# TMS.net
KiCad netlist of a schematic drawn in Altium Designer
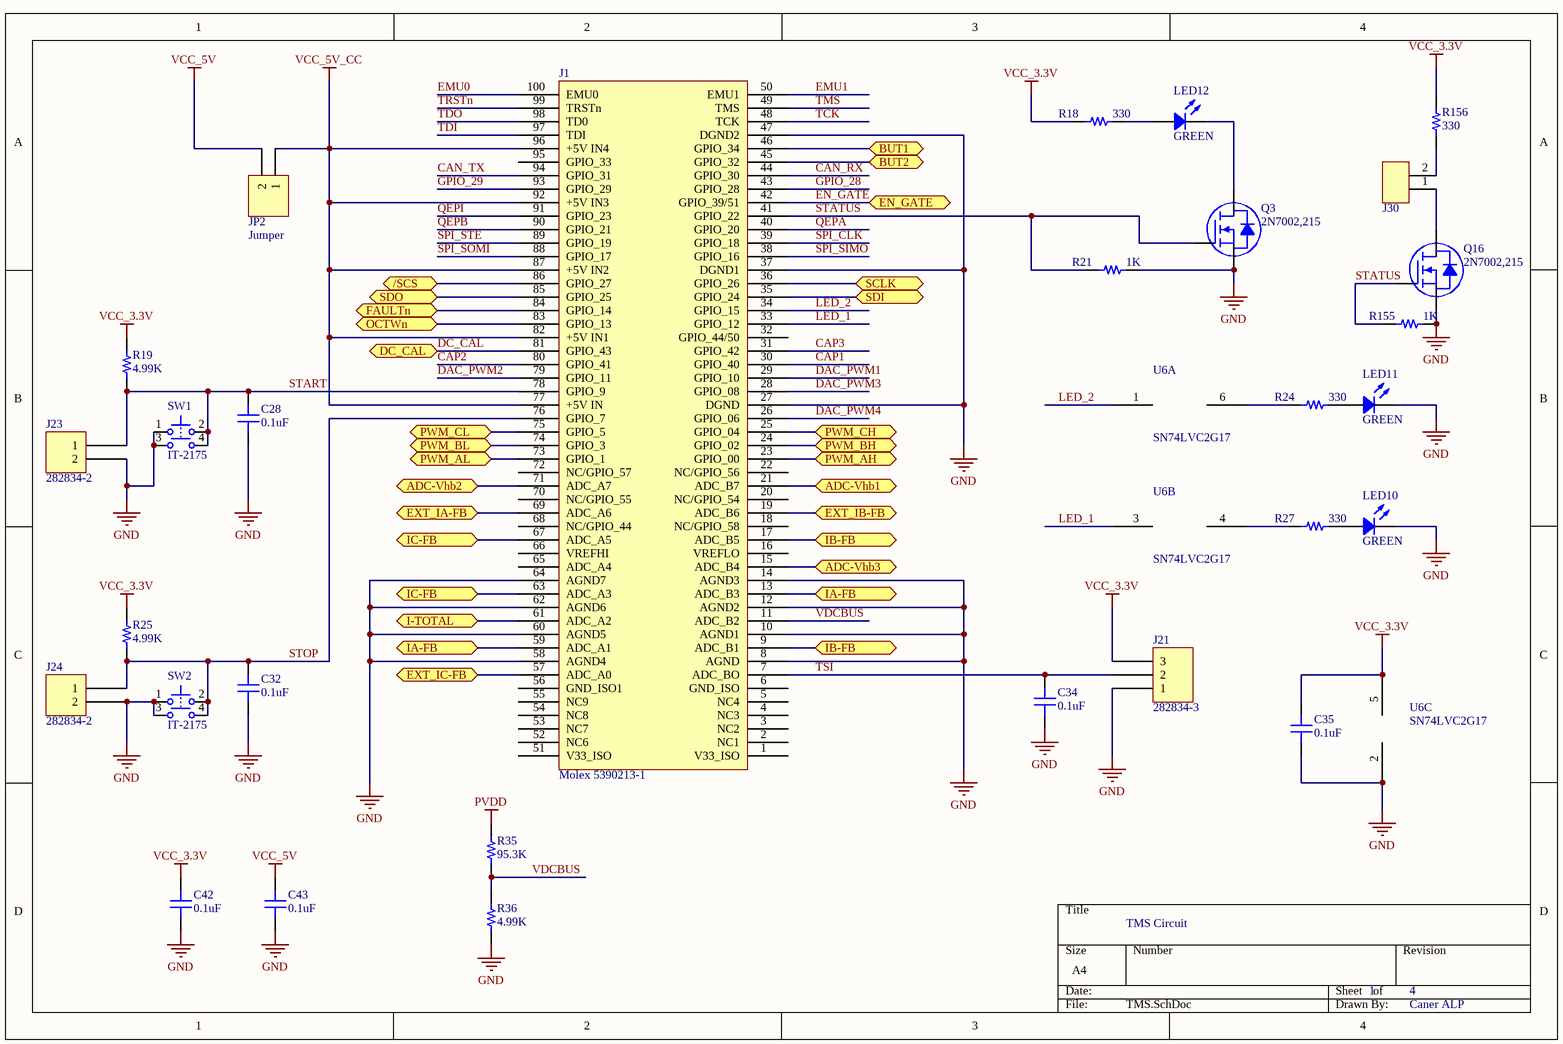
[diagram p0: TMS.SchDoc]

(export (version "E")
  (design (tool "Eeschema 10.0.6"))
  (components
    (comp (ref "C28")
      (value "0.1uF")
      (footprint "CAP 0603/1608")
      (description "CAP CER 0.1UF 16V X7R 0603")
      (fields (field (name "PART NUMBER") "CC0603KPX7R7BB104") (field (name "MANUFACTURER") "Yageo"))
      (libsource (lib "Celestial Library Database") (part "Capacitor"))
    )
    (comp (ref "C32")
      (value "0.1uF")
      (footprint "CAP 0603/1608")
      (description "CAP CER 0.1UF 16V X7R 0603")
      (fields (field (name "PART NUMBER") "CC0603KPX7R7BB104") (field (name "MANUFACTURER") "Yageo"))
      (libsource (lib "Celestial Library Database") (part "Capacitor"))
    )
    (comp (ref "C34")
      (value "0.1uF")
      (footprint "CAP 0603/1608")
      (description "CAP CER 0.1UF 16V X7R 0603")
      (fields (field (name "PART NUMBER") "CC0603KPX7R7BB104") (field (name "MANUFACTURER") "Yageo"))
      (libsource (lib "Celestial Library Database") (part "Capacitor"))
    )
    (comp (ref "C35")
      (value "0.1uF")
      (footprint "CAP 0603/1608")
      (description "CAP CER 0.1UF 16V X7R 0603")
      (fields (field (name "PART NUMBER") "CC0603KPX7R7BB104") (field (name "MANUFACTURER") "Yageo"))
      (libsource (lib "Celestial Library Database") (part "Capacitor"))
    )
    (comp (ref "C42")
      (value "0.1uF")
      (footprint "CAP 0603/1608")
      (description "CAP CER 0.1UF 16V X7R 0603")
      (fields (field (name "PART NUMBER") "CC0603KPX7R7BB104") (field (name "MANUFACTURER") "Yageo"))
      (libsource (lib "Celestial Library Database") (part "Capacitor"))
    )
    (comp (ref "C43")
      (value "0.1uF")
      (footprint "CAP 0603/1608")
      (description "CAP CER 0.1UF 16V X7R 0603")
      (fields (field (name "PART NUMBER") "CC0603KPX7R7BB104") (field (name "MANUFACTURER") "Yageo"))
      (libsource (lib "Celestial Library Database") (part "Capacitor"))
    )
    (comp (ref "J1")
      (value "Molex 5390213-1")
      (footprint "DIMM100")
      (description "DIMM Connectors DIMM SKT 100P 2.54mm")
      (libsource (lib "Altium Component") (part "DIMM100 DRAM"))
    )
    (comp (ref "J21")
      (value "282834-3")
      (footprint "TE 282834-3")
      (description "TERM BLOCK 3POS SIDE ENT 2.54MM")
      (fields (field (name "MANUFACTURER") "TE Connectivity AMP Connectors") (field (name "VOLTAGE") "150V"))
      (libsource (lib "Celestial Library Database") (part "3 Pin"))
    )
    (comp (ref "J23")
      (value "282834-2")
      (footprint "TE 282834-2")
      (description "TERM BLOCK 2POS SIDE ENT 2.54MM")
      (fields (field (name "MANUFACTURER") "TE Connectivity AMP Connectors") (field (name "VOLTAGE") "150V"))
      (libsource (lib "Celestial Library Database") (part "2 Pin"))
    )
    (comp (ref "J24")
      (value "282834-2")
      (footprint "TE 282834-2")
      (description "TERM BLOCK 2POS SIDE ENT 2.54MM")
      (fields (field (name "MANUFACTURER") "TE Connectivity AMP Connectors") (field (name "VOLTAGE") "150V"))
      (libsource (lib "Celestial Library Database") (part "2 Pin"))
    )
    (comp (ref "J30")
      (value "HDR_1x2")
      (footprint "PINHEAD_2.54mm_1x2")
      (description "CONN HEADER 2POS .100 VERT TIN")
      (fields (field (name "PART NUMBER") "J00093") (field (name "MANUFACTURER") "Molex, LLC"))
      (libsource (lib "open-components") (part "HDR_1x2"))
    )
    (comp (ref "JP2")
      (value "Jumper")
      (footprint "Header 2.54mm - duplicate")
      (description "Header, 2-Pin")
      (fields (field (name "PUBLISHER") "Altium Limited"))
      (libsource (lib "Miscellaneous Connectors") (part "Header 2"))
    )
    (comp (ref "LED10")
      (value "GREEN")
      (footprint "LED 0805/2012 YELLOW")
      (description "LED ORANGE CLEAR 0805 SMD")
      (fields (field (name "PART NUMBER") "LTST-C170KFKT") (field (name "MANUFACTURER") "Lite-On Inc."))
      (libsource (lib "Celestial Library Database") (part "LED"))
    )
    (comp (ref "LED11")
      (value "GREEN")
      (footprint "LED 0805/2012 YELLOW")
      (description "LED ORANGE CLEAR 0805 SMD")
      (fields (field (name "PART NUMBER") "LTST-C170KFKT") (field (name "MANUFACTURER") "Lite-On Inc."))
      (libsource (lib "Celestial Library Database") (part "LED"))
    )
    (comp (ref "LED12")
      (value "GREEN")
      (footprint "LED 0805/2012 YELLOW")
      (description "LED ORANGE CLEAR 0805 SMD")
      (fields (field (name "PART NUMBER") "LTST-C170KFKT") (field (name "MANUFACTURER") "Lite-On Inc."))
      (libsource (lib "Celestial Library Database") (part "LED"))
    )
    (comp (ref "Q3")
      (value "2N7002,215")
      (footprint "NXP SOT-23-3 TO-236AB")
      (description "MOSFET N-CH 60V 300MA SOT-23")
      (fields (field (name "MANUFACTURER") "NXP Semiconductors"))
      (libsource (lib "Celestial Library Database") (part "NXP MOSFET N-CH SOT-23-3"))
    )
    (comp (ref "Q16")
      (value "2N7002,215")
      (footprint "NXP SOT-23-3 TO-236AB")
      (description "MOSFET N-CH 60V 300MA SOT-23")
      (fields (field (name "MANUFACTURER") "NXP Semiconductors"))
      (libsource (lib "Celestial Library Database") (part "NXP MOSFET N-CH SOT-23-3"))
    )
    (comp (ref "R18")
      (value "330")
      (footprint "RES 0603/1608")
      (description "RES SMD 330 OHM 5% 1/10W 0603")
      (fields
        (field (name "PART NUMBER") "ERJ-3GEYJ331V")
        (field (name "MANUFACTURER") "Panasonic Electronic Components")
      )
      (libsource (lib "Celestial Library Database") (part "Resistor"))
    )
    (comp (ref "R19")
      (value "4.99K")
      (footprint "RES 0603/1608")
      (description "RES SMD 330 OHM 5% 1/10W 0603")
      (fields
        (field (name "PART NUMBER") "ERJ-3GEYJ331V")
        (field (name "MANUFACTURER") "Panasonic Electronic Components")
      )
      (libsource (lib "Celestial Library Database") (part "Resistor"))
    )
    (comp (ref "R21")
      (value "1K")
      (footprint "RES 0603/1608")
      (description "RES SMD 330 OHM 5% 1/10W 0603")
      (fields
        (field (name "PART NUMBER") "ERJ-3GEYJ331V")
        (field (name "MANUFACTURER") "Panasonic Electronic Components")
      )
      (libsource (lib "Celestial Library Database") (part "Resistor"))
    )
    (comp (ref "R24")
      (value "330")
      (footprint "RES 0603/1608")
      (description "RES SMD 330 OHM 5% 1/10W 0603")
      (fields
        (field (name "PART NUMBER") "ERJ-3GEYJ331V")
        (field (name "MANUFACTURER") "Panasonic Electronic Components")
      )
      (libsource (lib "Celestial Library Database") (part "Resistor"))
    )
    (comp (ref "R25")
      (value "4.99K")
      (footprint "RES 0603/1608")
      (description "RES SMD 330 OHM 5% 1/10W 0603")
      (fields
        (field (name "PART NUMBER") "ERJ-3GEYJ331V")
        (field (name "MANUFACTURER") "Panasonic Electronic Components")
      )
      (libsource (lib "Celestial Library Database") (part "Resistor"))
    )
    (comp (ref "R27")
      (value "330")
      (footprint "RES 0603/1608")
      (description "RES SMD 330 OHM 5% 1/10W 0603")
      (fields
        (field (name "PART NUMBER") "ERJ-3GEYJ331V")
        (field (name "MANUFACTURER") "Panasonic Electronic Components")
      )
      (libsource (lib "Celestial Library Database") (part "Resistor"))
    )
    (comp (ref "R35")
      (value "95.3K")
      (footprint "RES 0603/1608")
      (description "RES SMD 330 OHM 5% 1/10W 0603")
      (fields
        (field (name "PART NUMBER") "ERJ-3GEYJ331V")
        (field (name "MANUFACTURER") "Panasonic Electronic Components")
      )
      (libsource (lib "Celestial Library Database") (part "Resistor"))
    )
    (comp (ref "R36")
      (value "4.99K")
      (footprint "RES 0603/1608")
      (description "RES SMD 330 OHM 5% 1/10W 0603")
      (fields
        (field (name "PART NUMBER") "ERJ-3GEYJ331V")
        (field (name "MANUFACTURER") "Panasonic Electronic Components")
      )
      (libsource (lib "Celestial Library Database") (part "Resistor"))
    )
    (comp (ref "R155")
      (value "1K")
      (footprint "RES 0603/1608")
      (description "RES SMD 330 OHM 5% 1/10W 0603")
      (fields
        (field (name "PART NUMBER") "ERJ-3GEYJ331V")
        (field (name "MANUFACTURER") "Panasonic Electronic Components")
      )
      (libsource (lib "Celestial Library Database") (part "Resistor"))
    )
    (comp (ref "R156")
      (value "330")
      (footprint "RES 0603/1608")
      (description "RES SMD 330 OHM 5% 1/10W 0603")
      (fields
        (field (name "PART NUMBER") "ERJ-3GEYJ331V")
        (field (name "MANUFACTURER") "Panasonic Electronic Components")
      )
      (libsource (lib "Celestial Library Database") (part "Resistor"))
    )
    (comp (ref "SW1")
      (value "IT-2175")
      (footprint "Tick Tole Switch")
      (description "Tactile Switch, DPST; Thru-Hole; Vertical; Rating DC 12V, 50mA (max)")
      (fields (field (name "PUBLISHER") "Altium Limited"))
      (libsource (lib "IL Switch Push Button") (part "IT-2175"))
    )
    (comp (ref "SW2")
      (value "IT-2175")
      (footprint "Tick Tole Switch")
      (description "Tactile Switch, DPST; Thru-Hole; Vertical; Rating DC 12V, 50mA (max)")
      (fields (field (name "PUBLISHER") "Altium Limited"))
      (libsource (lib "IL Switch Push Button") (part "IT-2175"))
    )
    (comp (ref "U6")
      (value "SN74LVC2G17")
      (footprint "DBV006")
      (libsource (lib "Altium Component") (part "SN74LVC2G17"))
    )
  )
  (nets
    (net (code "1") (name "/ADC-Vhb1") (class "Default")
      (node (ref "J1") (pin "21") (pinfunction "ADC_B7_21") (pintype "passive"))
    )
    (net (code "2") (name "/ADC-Vhb2") (class "Default")
      (node (ref "J1") (pin "71") (pinfunction "ADC_A7_71") (pintype "passive"))
    )
    (net (code "3") (name "/ADC-Vhb3") (class "Default")
      (node (ref "J1") (pin "15") (pinfunction "ADC_B4_15") (pintype "passive"))
    )
    (net (code "4") (name "/BUT1") (class "Default")
      (node (ref "J1") (pin "46") (pinfunction "GPIO_34_46") (pintype "passive"))
    )
    (net (code "5") (name "/BUT2") (class "Default")
      (node (ref "J1") (pin "45") (pinfunction "GPIO_32_45") (pintype "passive"))
    )
    (net (code "6") (name "/CAN_RX") (class "Default")
      (node (ref "J1") (pin "44") (pinfunction "GPIO_30_44") (pintype "passive"))
    )
    (net (code "7") (name "/CAN_TX") (class "Default")
      (node (ref "J1") (pin "94") (pinfunction "GPIO_31_94") (pintype "passive"))
    )
    (net (code "8") (name "/CAP1") (class "Default")
      (node (ref "J1") (pin "30") (pinfunction "GPIO_40_30") (pintype "passive"))
    )
    (net (code "9") (name "/CAP2") (class "Default")
      (node (ref "J1") (pin "80") (pinfunction "GPIO_41_80") (pintype "passive"))
    )
    (net (code "10") (name "/CAP3") (class "Default")
      (node (ref "J1") (pin "31") (pinfunction "GPIO_42_31") (pintype "passive"))
    )
    (net (code "11") (name "/DAC_PWM1") (class "Default")
      (node (ref "J1") (pin "29") (pinfunction "GPIO_10_29") (pintype "passive"))
    )
    (net (code "12") (name "/DAC_PWM2") (class "Default")
      (node (ref "J1") (pin "79") (pinfunction "GPIO_11_79") (pintype "passive"))
    )
    (net (code "13") (name "/DAC_PWM3") (class "Default")
      (node (ref "J1") (pin "28") (pinfunction "GPIO_08_28") (pintype "passive"))
    )
    (net (code "14") (name "/DAC_PWM4") (class "Default")
      (node (ref "J1") (pin "26") (pinfunction "GPIO_06_26") (pintype "passive"))
    )
    (net (code "15") (name "/DC_CAL") (class "Default")
      (node (ref "J1") (pin "81") (pinfunction "GPIO_43_81") (pintype "passive"))
    )
    (net (code "16") (name "/EMU0") (class "Default")
      (node (ref "J1") (pin "100") (pinfunction "EMU0_100") (pintype "passive"))
    )
    (net (code "17") (name "/EMU1") (class "Default")
      (node (ref "J1") (pin "50") (pinfunction "EMU1_50") (pintype "passive"))
    )
    (net (code "18") (name "/EN_GATE") (class "Default")
      (node (ref "J1") (pin "42") (pinfunction "GPIO_39/51_42") (pintype "passive"))
    )
    (net (code "19") (name "/EXT_IA-FB") (class "Default")
      (node (ref "J1") (pin "69") (pinfunction "ADC_A6_69") (pintype "passive"))
    )
    (net (code "20") (name "/EXT_IB-FB") (class "Default")
      (node (ref "J1") (pin "19") (pinfunction "ADC_B6_19") (pintype "passive"))
    )
    (net (code "21") (name "/EXT_IC-FB") (class "Default")
      (node (ref "J1") (pin "57") (pinfunction "ADC_A0_57") (pintype "passive"))
    )
    (net (code "22") (name "/FAULTn") (class "Default")
      (node (ref "J1") (pin "84") (pinfunction "GPIO_14_84") (pintype "passive"))
    )
    (net (code "23") (name "/GPIO_28") (class "Default")
      (node (ref "J1") (pin "43") (pinfunction "GPIO_28_43") (pintype "passive"))
    )
    (net (code "24") (name "/GPIO_29") (class "Default")
      (node (ref "J1") (pin "93") (pinfunction "GPIO_29_93") (pintype "passive"))
    )
    (net (code "25") (name "/I-TOTAL") (class "Default")
      (node (ref "J1") (pin "61") (pinfunction "ADC_A2_61") (pintype "passive"))
    )
    (net (code "26") (name "/IA-FB") (class "Default")
      (node (ref "J1") (pin "13") (pinfunction "ADC_B3_13") (pintype "passive"))
      (node (ref "J1") (pin "59") (pinfunction "ADC_A1_59") (pintype "passive"))
    )
    (net (code "27") (name "/IB-FB") (class "Default")
      (node (ref "J1") (pin "17") (pinfunction "ADC_B5_17") (pintype "passive"))
      (node (ref "J1") (pin "9") (pinfunction "ADC_B1_9") (pintype "passive"))
    )
    (net (code "28") (name "/IC-FB") (class "Default")
      (node (ref "J1") (pin "63") (pinfunction "ADC_A3_63") (pintype "passive"))
      (node (ref "J1") (pin "67") (pinfunction "ADC_A5_67") (pintype "passive"))
    )
    (net (code "29") (name "/LED_1") (class "Default")
      (node (ref "J1") (pin "33") (pinfunction "GPIO_12_33") (pintype "passive"))
      (node (ref "U6") (pin "3") (pinfunction "EMU1_3") (pintype "passive"))
    )
    (net (code "30") (name "/LED_2") (class "Default")
      (node (ref "J1") (pin "34") (pinfunction "GPIO_15_34") (pintype "passive"))
      (node (ref "U6") (pin "1") (pinfunction "EMU1_1") (pintype "passive"))
    )
    (net (code "31") (name "/OCTWn") (class "Default")
      (node (ref "J1") (pin "83") (pinfunction "GPIO_13_83") (pintype "passive"))
    )
    (net (code "32") (name "/PWM_AH") (class "Default")
      (node (ref "J1") (pin "23") (pinfunction "GPIO_00_23") (pintype "passive"))
    )
    (net (code "33") (name "/PWM_AL") (class "Default")
      (node (ref "J1") (pin "73") (pinfunction "GPIO_1_73") (pintype "passive"))
    )
    (net (code "34") (name "/PWM_BH") (class "Default")
      (node (ref "J1") (pin "24") (pinfunction "GPIO_02_24") (pintype "passive"))
    )
    (net (code "35") (name "/PWM_BL") (class "Default")
      (node (ref "J1") (pin "74") (pinfunction "GPIO_3_74") (pintype "passive"))
    )
    (net (code "36") (name "/PWM_CH") (class "Default")
      (node (ref "J1") (pin "25") (pinfunction "GPIO_04_25") (pintype "passive"))
    )
    (net (code "37") (name "/PWM_CL") (class "Default")
      (node (ref "J1") (pin "75") (pinfunction "GPIO_5_75") (pintype "passive"))
    )
    (net (code "38") (name "/QEPA") (class "Default")
      (node (ref "J1") (pin "40") (pinfunction "GPIO_20_40") (pintype "passive"))
    )
    (net (code "39") (name "/QEPB") (class "Default")
      (node (ref "J1") (pin "90") (pinfunction "GPIO_21_90") (pintype "passive"))
    )
    (net (code "40") (name "/QEPI") (class "Default")
      (node (ref "J1") (pin "91") (pinfunction "GPIO_23_91") (pintype "passive"))
    )
    (net (code "41") (name "/SCLK") (class "Default")
      (node (ref "J1") (pin "36") (pinfunction "GPIO_26_36") (pintype "passive"))
    )
    (net (code "42") (name "/SDI") (class "Default")
      (node (ref "J1") (pin "35") (pinfunction "GPIO_24_35") (pintype "passive"))
    )
    (net (code "43") (name "/SDO") (class "Default")
      (node (ref "J1") (pin "85") (pinfunction "GPIO_25_85") (pintype "passive"))
    )
    (net (code "44") (name "/SPI_CLK") (class "Default")
      (node (ref "J1") (pin "39") (pinfunction "GPIO_18_39") (pintype "passive"))
    )
    (net (code "45") (name "/SPI_SIMO") (class "Default")
      (node (ref "J1") (pin "38") (pinfunction "GPIO_16_38") (pintype "passive"))
    )
    (net (code "46") (name "/SPI_SOMI") (class "Default")
      (node (ref "J1") (pin "88") (pinfunction "GPIO_17_88") (pintype "passive"))
    )
    (net (code "47") (name "/SPI_STE") (class "Default")
      (node (ref "J1") (pin "89") (pinfunction "GPIO_19_89") (pintype "passive"))
    )
    (net (code "48") (name "/START") (class "Default")
      (node (ref "C28") (pin "2") (pinfunction "2_2") (pintype "passive"))
      (node (ref "J1") (pin "78") (pinfunction "GPIO_9_78") (pintype "passive"))
      (node (ref "J23") (pin "1") (pinfunction "1_1") (pintype "passive"))
      (node (ref "R19") (pin "1") (pinfunction "1_1") (pintype "passive"))
      (node (ref "SW1") (pin "2") (pinfunction "2_2") (pintype "passive"))
      (node (ref "SW1") (pin "4") (pinfunction "4_4") (pintype "passive"))
    )
    (net (code "49") (name "/STATUS") (class "Default")
      (node (ref "J1") (pin "41") (pinfunction "GPIO_22_41") (pintype "passive"))
      (node (ref "Q16") (pin "1") (pinfunction "G_1") (pintype "passive"))
      (node (ref "Q3") (pin "1") (pinfunction "G_1") (pintype "passive"))
      (node (ref "R155") (pin "1") (pinfunction "1_1") (pintype "passive"))
      (node (ref "R21") (pin "1") (pinfunction "1_1") (pintype "passive"))
    )
    (net (code "50") (name "/STOP") (class "Default")
      (node (ref "C32") (pin "2") (pinfunction "2_2") (pintype "passive"))
      (node (ref "J1") (pin "76") (pinfunction "GPIO_7_76") (pintype "passive"))
      (node (ref "J24") (pin "1") (pinfunction "1_1") (pintype "passive"))
      (node (ref "R25") (pin "1") (pinfunction "1_1") (pintype "passive"))
      (node (ref "SW2") (pin "2") (pinfunction "2_2") (pintype "passive"))
      (node (ref "SW2") (pin "4") (pinfunction "4_4") (pintype "passive"))
    )
    (net (code "51") (name "/TCK") (class "Default")
      (node (ref "J1") (pin "48") (pinfunction "TCK_48") (pintype "passive"))
    )
    (net (code "52") (name "/TDI") (class "Default")
      (node (ref "J1") (pin "97") (pinfunction "TDI_97") (pintype "passive"))
    )
    (net (code "53") (name "/TDO") (class "Default")
      (node (ref "J1") (pin "98") (pinfunction "TD0_98") (pintype "passive"))
    )
    (net (code "54") (name "/TMS") (class "Default")
      (node (ref "J1") (pin "49") (pinfunction "TMS_49") (pintype "passive"))
    )
    (net (code "55") (name "/TRSTn") (class "Default")
      (node (ref "J1") (pin "99") (pinfunction "TRSTn_99") (pintype "passive"))
    )
    (net (code "56") (name "/TSI") (class "Default")
      (node (ref "C34") (pin "2") (pinfunction "2_2") (pintype "passive"))
      (node (ref "J1") (pin "7") (pinfunction "ADC_BO_7") (pintype "passive"))
      (node (ref "J21") (pin "2") (pinfunction "2_2") (pintype "passive"))
    )
    (net (code "57") (name "/VDCBUS") (class "Default")
      (node (ref "J1") (pin "11") (pinfunction "ADC_B2_11") (pintype "passive"))
      (node (ref "R35") (pin "2") (pinfunction "2_2") (pintype "passive"))
      (node (ref "R36") (pin "1") (pinfunction "1_1") (pintype "passive"))
    )
    (net (code "58") (name "/{slash}SCS") (class "Default")
      (node (ref "J1") (pin "86") (pinfunction "GPIO_27_86") (pintype "passive"))
    )
    (net (code "59") (name "GND") (class "Default")
      (node (ref "C28") (pin "1") (pinfunction "1_1") (pintype "passive"))
      (node (ref "C32") (pin "1") (pinfunction "1_1") (pintype "passive"))
      (node (ref "C34") (pin "1") (pinfunction "1_1") (pintype "passive"))
      (node (ref "C35") (pin "1") (pinfunction "1_1") (pintype "passive"))
      (node (ref "C42") (pin "1") (pinfunction "1_1") (pintype "passive"))
      (node (ref "C43") (pin "1") (pinfunction "1_1") (pintype "passive"))
      (node (ref "J1") (pin "10") (pinfunction "AGND1_10") (pintype "passive"))
      (node (ref "J1") (pin "12") (pinfunction "AGND2_12") (pintype "passive"))
      (node (ref "J1") (pin "14") (pinfunction "AGND3_14") (pintype "passive"))
      (node (ref "J1") (pin "27") (pinfunction "DGND_27") (pintype "passive"))
      (node (ref "J1") (pin "37") (pinfunction "DGND1_37") (pintype "passive"))
      (node (ref "J1") (pin "47") (pinfunction "DGND2_47") (pintype "passive"))
      (node (ref "J1") (pin "58") (pinfunction "AGND4_58") (pintype "passive"))
      (node (ref "J1") (pin "60") (pinfunction "AGND5_60") (pintype "passive"))
      (node (ref "J1") (pin "62") (pinfunction "AGND6_62") (pintype "passive"))
      (node (ref "J1") (pin "64") (pinfunction "AGND7_64") (pintype "passive"))
      (node (ref "J1") (pin "8") (pinfunction "AGND_8") (pintype "passive"))
      (node (ref "J21") (pin "1") (pinfunction "1_1") (pintype "passive"))
      (node (ref "J23") (pin "2") (pinfunction "2_2") (pintype "passive"))
      (node (ref "J24") (pin "2") (pinfunction "2_2") (pintype "passive"))
      (node (ref "LED10") (pin "2") (pinfunction "2_2") (pintype "passive"))
      (node (ref "LED11") (pin "2") (pinfunction "2_2") (pintype "passive"))
      (node (ref "Q16") (pin "3") (pinfunction "S_3") (pintype "passive"))
      (node (ref "Q3") (pin "3") (pinfunction "S_3") (pintype "passive"))
      (node (ref "R155") (pin "2") (pinfunction "2_2") (pintype "passive"))
      (node (ref "R21") (pin "2") (pinfunction "2_2") (pintype "passive"))
      (node (ref "R36") (pin "2") (pinfunction "2_2") (pintype "passive"))
      (node (ref "SW1") (pin "1") (pinfunction "1_1") (pintype "passive"))
      (node (ref "SW1") (pin "3") (pinfunction "3_3") (pintype "passive"))
      (node (ref "SW2") (pin "1") (pinfunction "1_1") (pintype "passive"))
      (node (ref "SW2") (pin "3") (pinfunction "3_3") (pintype "passive"))
      (node (ref "U6") (pin "2") (pinfunction "EMU2_2") (pintype "passive"))
    )
    (net (code "60") (name "Net-(J30-Pad2)") (class "Default")
      (node (ref "J30") (pin "2") (pinfunction "2_2") (pintype "passive"))
      (node (ref "R156") (pin "1") (pinfunction "1_1") (pintype "passive"))
    )
    (net (code "61") (name "Net-(LED10-Pad1)") (class "Default")
      (node (ref "LED10") (pin "1") (pinfunction "1_1") (pintype "passive"))
      (node (ref "R27") (pin "2") (pinfunction "2_2") (pintype "passive"))
    )
    (net (code "62") (name "Net-(LED11-Pad1)") (class "Default")
      (node (ref "LED11") (pin "1") (pinfunction "1_1") (pintype "passive"))
      (node (ref "R24") (pin "2") (pinfunction "2_2") (pintype "passive"))
    )
    (net (code "63") (name "Net-(LED12-Pad1)") (class "Default")
      (node (ref "LED12") (pin "1") (pinfunction "1_1") (pintype "passive"))
      (node (ref "R18") (pin "2") (pinfunction "2_2") (pintype "passive"))
    )
    (net (code "64") (name "Net-(Q3-D)") (class "Default")
      (node (ref "LED12") (pin "2") (pinfunction "2_2") (pintype "passive"))
      (node (ref "Q3") (pin "2") (pinfunction "D_2") (pintype "passive"))
    )
    (net (code "65") (name "Net-(Q16-D)") (class "Default")
      (node (ref "J30") (pin "1") (pinfunction "1_1") (pintype "passive"))
      (node (ref "Q16") (pin "2") (pinfunction "D_2") (pintype "passive"))
    )
    (net (code "66") (name "Net-(U6A-EMU2)") (class "Default")
      (node (ref "R24") (pin "1") (pinfunction "1_1") (pintype "passive"))
      (node (ref "U6") (pin "6") (pinfunction "EMU2_6") (pintype "passive"))
    )
    (net (code "67") (name "Net-(U6B-EMU2)") (class "Default")
      (node (ref "R27") (pin "1") (pinfunction "1_1") (pintype "passive"))
      (node (ref "U6") (pin "4") (pinfunction "EMU2_4") (pintype "passive"))
    )
    (net (code "68") (name "PVDD") (class "Default")
      (node (ref "R35") (pin "1") (pinfunction "1_1") (pintype "passive"))
    )
    (net (code "69") (name "VCC_3.3V") (class "Default")
      (node (ref "C35") (pin "2") (pinfunction "2_2") (pintype "passive"))
      (node (ref "C42") (pin "2") (pinfunction "2_2") (pintype "passive"))
      (node (ref "J21") (pin "3") (pinfunction "3_3") (pintype "passive"))
      (node (ref "R156") (pin "2") (pinfunction "2_2") (pintype "passive"))
      (node (ref "R18") (pin "1") (pinfunction "1_1") (pintype "passive"))
      (node (ref "R19") (pin "2") (pinfunction "2_2") (pintype "passive"))
      (node (ref "R25") (pin "2") (pinfunction "2_2") (pintype "passive"))
      (node (ref "U6") (pin "5") (pinfunction "EMU1_5") (pintype "passive"))
    )
    (net (code "70") (name "VCC_5V") (class "Default")
      (node (ref "C43") (pin "2") (pinfunction "2_2") (pintype "passive"))
      (node (ref "JP2") (pin "2") (pinfunction "2_2") (pintype "passive"))
    )
    (net (code "71") (name "VCC_5V_CC") (class "Default")
      (node (ref "J1") (pin "77") (pinfunction "+5V_IN_77") (pintype "passive"))
      (node (ref "J1") (pin "82") (pinfunction "+5V_IN1_82") (pintype "passive"))
      (node (ref "J1") (pin "87") (pinfunction "+5V_IN2_87") (pintype "passive"))
      (node (ref "J1") (pin "92") (pinfunction "+5V_IN3_92") (pintype "passive"))
      (node (ref "J1") (pin "96") (pinfunction "+5V_IN4_96") (pintype "passive"))
      (node (ref "JP2") (pin "1") (pinfunction "1_1") (pintype "passive"))
    )
    (net (code "72") (name "unconnected-(J1-ADC_A4-Pad65)") (class "Default")
      (node (ref "J1") (pin "65") (pinfunction "ADC_A4_65") (pintype "passive"))
    )
    (net (code "73") (name "unconnected-(J1-GND_ISO-Pad6)") (class "Default")
      (node (ref "J1") (pin "6") (pinfunction "GND_ISO_6") (pintype "passive"))
    )
    (net (code "74") (name "unconnected-(J1-GND_ISO1-Pad56)") (class "Default")
      (node (ref "J1") (pin "56") (pinfunction "GND_ISO1_56") (pintype "passive"))
    )
    (net (code "75") (name "unconnected-(J1-GPIO_33-Pad95)") (class "Default")
      (node (ref "J1") (pin "95") (pinfunction "GPIO_33_95") (pintype "passive"))
    )
    (net (code "76") (name "unconnected-(J1-GPIO_44{slash}50-Pad32)") (class "Default")
      (node (ref "J1") (pin "32") (pinfunction "GPIO_44/50_32") (pintype "passive"))
    )
    (net (code "77") (name "unconnected-(J1-NC1-Pad2)") (class "Default")
      (node (ref "J1") (pin "2") (pinfunction "NC1_2") (pintype "passive"))
    )
    (net (code "78") (name "unconnected-(J1-NC2-Pad3)") (class "Default")
      (node (ref "J1") (pin "3") (pinfunction "NC2_3") (pintype "passive"))
    )
    (net (code "79") (name "unconnected-(J1-NC3-Pad4)") (class "Default")
      (node (ref "J1") (pin "4") (pinfunction "NC3_4") (pintype "passive"))
    )
    (net (code "80") (name "unconnected-(J1-NC4-Pad5)") (class "Default")
      (node (ref "J1") (pin "5") (pinfunction "NC4_5") (pintype "passive"))
    )
    (net (code "81") (name "unconnected-(J1-NC6-Pad52)") (class "Default")
      (node (ref "J1") (pin "52") (pinfunction "NC6_52") (pintype "passive"))
    )
    (net (code "82") (name "unconnected-(J1-NC7-Pad53)") (class "Default")
      (node (ref "J1") (pin "53") (pinfunction "NC7_53") (pintype "passive"))
    )
    (net (code "83") (name "unconnected-(J1-NC8-Pad54)") (class "Default")
      (node (ref "J1") (pin "54") (pinfunction "NC8_54") (pintype "passive"))
    )
    (net (code "84") (name "unconnected-(J1-NC9-Pad55)") (class "Default")
      (node (ref "J1") (pin "55") (pinfunction "NC9_55") (pintype "passive"))
    )
    (net (code "85") (name "unconnected-(J1-NC{slash}GPIO_44-Pad68)") (class "Default")
      (node (ref "J1") (pin "68") (pinfunction "NC/GPIO_44_68") (pintype "passive"))
    )
    (net (code "86") (name "unconnected-(J1-NC{slash}GPIO_54-Pad20)") (class "Default")
      (node (ref "J1") (pin "20") (pinfunction "NC/GPIO_54_20") (pintype "passive"))
    )
    (net (code "87") (name "unconnected-(J1-NC{slash}GPIO_55-Pad70)") (class "Default")
      (node (ref "J1") (pin "70") (pinfunction "NC/GPIO_55_70") (pintype "passive"))
    )
    (net (code "88") (name "unconnected-(J1-NC{slash}GPIO_56-Pad22)") (class "Default")
      (node (ref "J1") (pin "22") (pinfunction "NC/GPIO_56_22") (pintype "passive"))
    )
    (net (code "89") (name "unconnected-(J1-NC{slash}GPIO_57-Pad72)") (class "Default")
      (node (ref "J1") (pin "72") (pinfunction "NC/GPIO_57_72") (pintype "passive"))
    )
    (net (code "90") (name "unconnected-(J1-NC{slash}GPIO_58-Pad18)") (class "Default")
      (node (ref "J1") (pin "18") (pinfunction "NC/GPIO_58_18") (pintype "passive"))
    )
    (net (code "91") (name "unconnected-(J1-V33_ISO-Pad1)") (class "Default")
      (node (ref "J1") (pin "1") (pinfunction "V33_ISO_1") (pintype "passive"))
    )
    (net (code "92") (name "unconnected-(J1-V33_ISO-Pad51)") (class "Default")
      (node (ref "J1") (pin "51") (pinfunction "V33_ISO_51") (pintype "passive"))
    )
    (net (code "93") (name "unconnected-(J1-VREFHI-Pad66)") (class "Default")
      (node (ref "J1") (pin "66") (pinfunction "VREFHI_66") (pintype "passive"))
    )
    (net (code "94") (name "unconnected-(J1-VREFLO-Pad16)") (class "Default")
      (node (ref "J1") (pin "16") (pinfunction "VREFLO_16") (pintype "passive"))
    )
  )
)
